# untitled.net
KiCad netlist of a schematic drawn in EAGLE
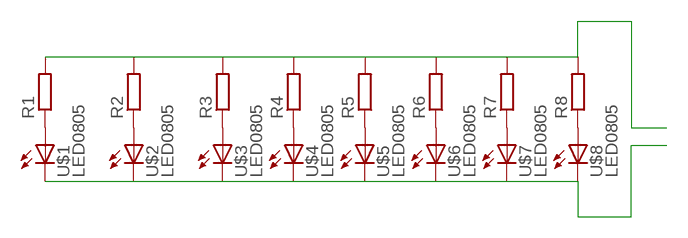
[diagram p0: schematic, sheet 1]

(export (version "E")
  (design (tool "Eeschema 10.0.6"))
  (components
    (comp (ref "R1")
      (value "R0603")
      (footprint "eagle-import:0603")
      (libsource (lib "eagle-import") (part "R0603"))
    )
    (comp (ref "R2")
      (value "R0603")
      (footprint "eagle-import:0603")
      (libsource (lib "eagle-import") (part "R0603"))
    )
    (comp (ref "R3")
      (value "R0603")
      (footprint "eagle-import:0603")
      (libsource (lib "eagle-import") (part "R0603"))
    )
    (comp (ref "R4")
      (value "R0603")
      (footprint "eagle-import:0603")
      (libsource (lib "eagle-import") (part "R0603"))
    )
    (comp (ref "R5")
      (value "R0603")
      (footprint "eagle-import:0603")
      (libsource (lib "eagle-import") (part "R0603"))
    )
    (comp (ref "R6")
      (value "R0603")
      (footprint "eagle-import:0603")
      (libsource (lib "eagle-import") (part "R0603"))
    )
    (comp (ref "R7")
      (value "R0603")
      (footprint "eagle-import:0603")
      (libsource (lib "eagle-import") (part "R0603"))
    )
    (comp (ref "R8")
      (value "R0603")
      (footprint "eagle-import:0603")
      (libsource (lib "eagle-import") (part "R0603"))
    )
    (comp (ref "U$1")
      (value "LED0805")
      (footprint "eagle-import:0805-LED")
      (libsource (lib "eagle-import") (part "LED0805"))
    )
    (comp (ref "U$2")
      (value "LED0805")
      (footprint "eagle-import:0805-LED")
      (libsource (lib "eagle-import") (part "LED0805"))
    )
    (comp (ref "U$3")
      (value "LED0805")
      (footprint "eagle-import:0805-LED")
      (libsource (lib "eagle-import") (part "LED0805"))
    )
    (comp (ref "U$4")
      (value "LED0805")
      (footprint "eagle-import:0805-LED")
      (libsource (lib "eagle-import") (part "LED0805"))
    )
    (comp (ref "U$5")
      (value "LED0805")
      (footprint "eagle-import:0805-LED")
      (libsource (lib "eagle-import") (part "LED0805"))
    )
    (comp (ref "U$6")
      (value "LED0805")
      (footprint "eagle-import:0805-LED")
      (libsource (lib "eagle-import") (part "LED0805"))
    )
    (comp (ref "U$7")
      (value "LED0805")
      (footprint "eagle-import:0805-LED")
      (libsource (lib "eagle-import") (part "LED0805"))
    )
    (comp (ref "U$8")
      (value "LED0805")
      (footprint "eagle-import:0805-LED")
      (libsource (lib "eagle-import") (part "LED0805"))
    )
  )
  (nets
    (net (code "1") (name "Net-(R1-Pad1)") (class "Default")
      (node (ref "R1") (pin "1") (pinfunction "1_1") (pintype "passive"))
      (node (ref "U$1") (pin "A") (pinfunction "A_A") (pintype "passive"))
    )
    (net (code "2") (name "Net-(R1-Pad2)") (class "Default")
      (node (ref "R1") (pin "2") (pinfunction "2_2") (pintype "passive"))
      (node (ref "R2") (pin "2") (pinfunction "2_2") (pintype "passive"))
      (node (ref "R3") (pin "2") (pinfunction "2_2") (pintype "passive"))
      (node (ref "R4") (pin "2") (pinfunction "2_2") (pintype "passive"))
      (node (ref "R5") (pin "2") (pinfunction "2_2") (pintype "passive"))
      (node (ref "R6") (pin "2") (pinfunction "2_2") (pintype "passive"))
      (node (ref "R7") (pin "2") (pinfunction "2_2") (pintype "passive"))
      (node (ref "R8") (pin "2") (pinfunction "2_2") (pintype "passive"))
    )
    (net (code "3") (name "Net-(R2-Pad1)") (class "Default")
      (node (ref "R2") (pin "1") (pinfunction "1_1") (pintype "passive"))
      (node (ref "U$2") (pin "A") (pinfunction "A_A") (pintype "passive"))
    )
    (net (code "4") (name "Net-(R3-Pad1)") (class "Default")
      (node (ref "R3") (pin "1") (pinfunction "1_1") (pintype "passive"))
      (node (ref "U$3") (pin "A") (pinfunction "A_A") (pintype "passive"))
    )
    (net (code "5") (name "Net-(R4-Pad1)") (class "Default")
      (node (ref "R4") (pin "1") (pinfunction "1_1") (pintype "passive"))
      (node (ref "U$4") (pin "A") (pinfunction "A_A") (pintype "passive"))
    )
    (net (code "6") (name "Net-(R5-Pad1)") (class "Default")
      (node (ref "R5") (pin "1") (pinfunction "1_1") (pintype "passive"))
      (node (ref "U$5") (pin "A") (pinfunction "A_A") (pintype "passive"))
    )
    (net (code "7") (name "Net-(R6-Pad1)") (class "Default")
      (node (ref "R6") (pin "1") (pinfunction "1_1") (pintype "passive"))
      (node (ref "U$6") (pin "A") (pinfunction "A_A") (pintype "passive"))
    )
    (net (code "8") (name "Net-(R7-Pad1)") (class "Default")
      (node (ref "R7") (pin "1") (pinfunction "1_1") (pintype "passive"))
      (node (ref "U$7") (pin "A") (pinfunction "A_A") (pintype "passive"))
    )
    (net (code "9") (name "Net-(R8-Pad1)") (class "Default")
      (node (ref "R8") (pin "1") (pinfunction "1_1") (pintype "passive"))
      (node (ref "U$8") (pin "A") (pinfunction "A_A") (pintype "passive"))
    )
    (net (code "10") (name "Net-(U$1-PadC)") (class "Default")
      (node (ref "U$1") (pin "C") (pinfunction "C_C") (pintype "passive"))
      (node (ref "U$2") (pin "C") (pinfunction "C_C") (pintype "passive"))
      (node (ref "U$3") (pin "C") (pinfunction "C_C") (pintype "passive"))
      (node (ref "U$4") (pin "C") (pinfunction "C_C") (pintype "passive"))
      (node (ref "U$5") (pin "C") (pinfunction "C_C") (pintype "passive"))
      (node (ref "U$6") (pin "C") (pinfunction "C_C") (pintype "passive"))
      (node (ref "U$7") (pin "C") (pinfunction "C_C") (pintype "passive"))
      (node (ref "U$8") (pin "C") (pinfunction "C_C") (pintype "passive"))
    )
  )
)
